# M7050E.net
KiCad netlist of a schematic drawn in EAGLE
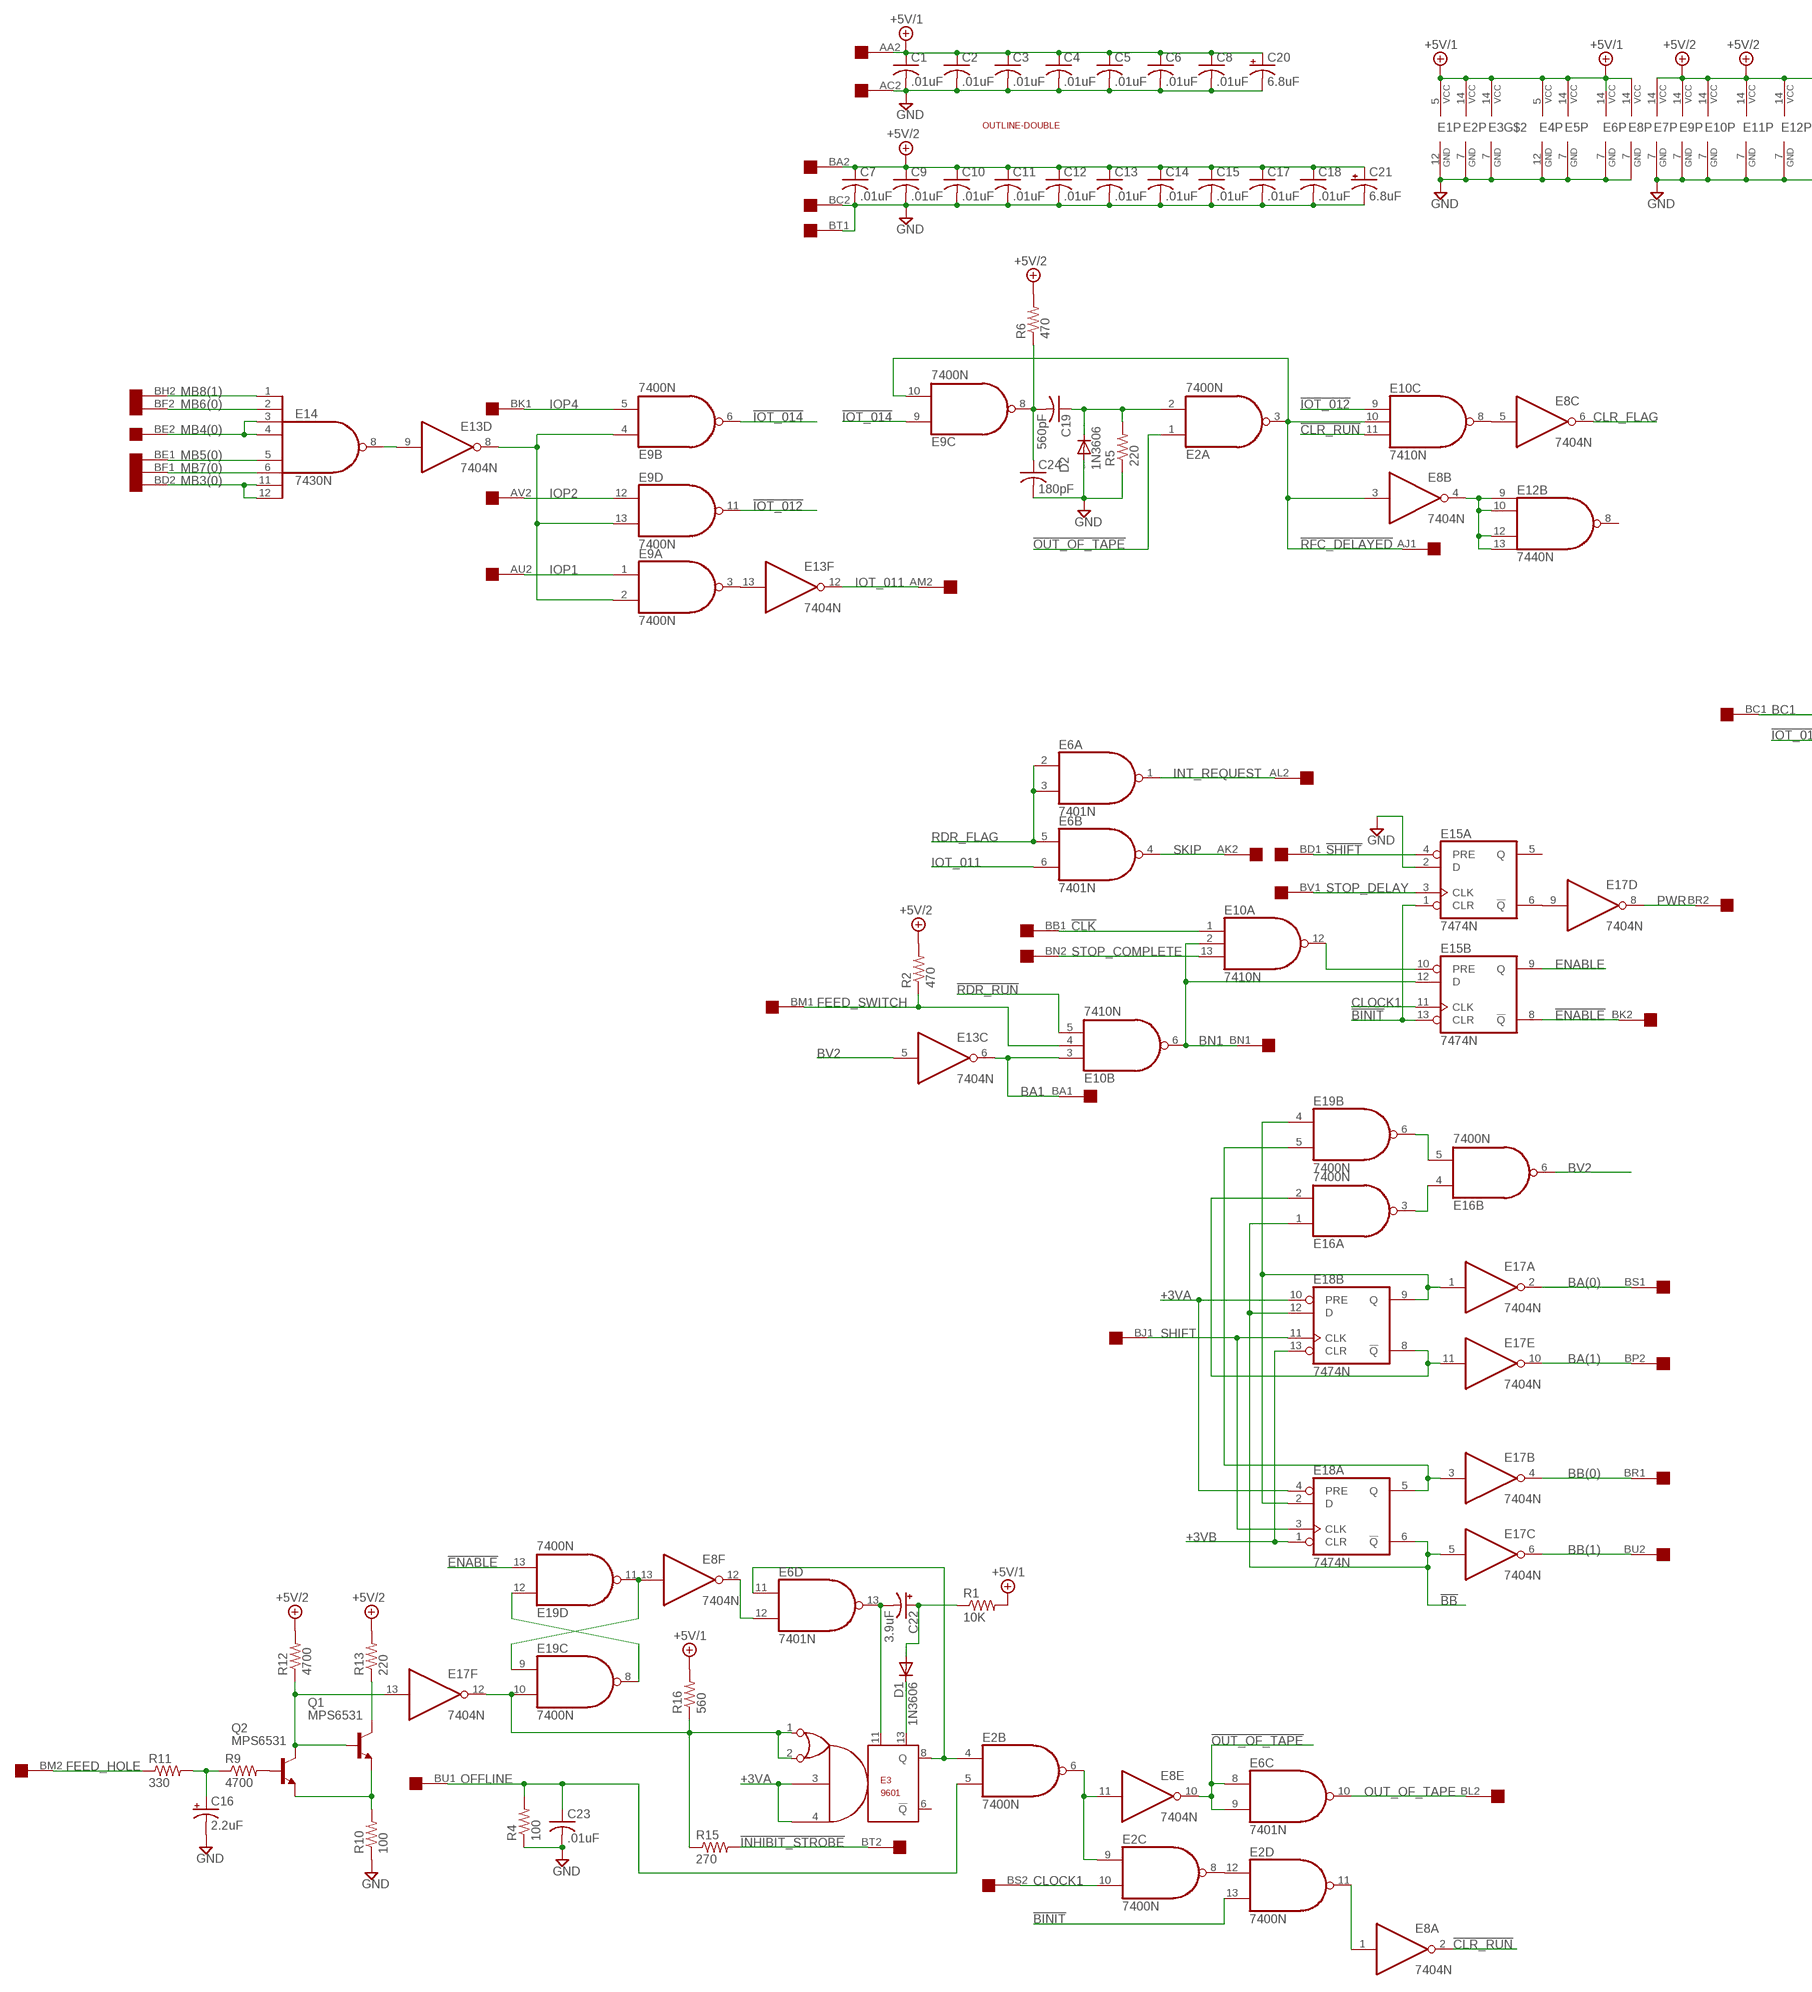
[diagram p0: schematic, sheet 1, part 1 of 2]
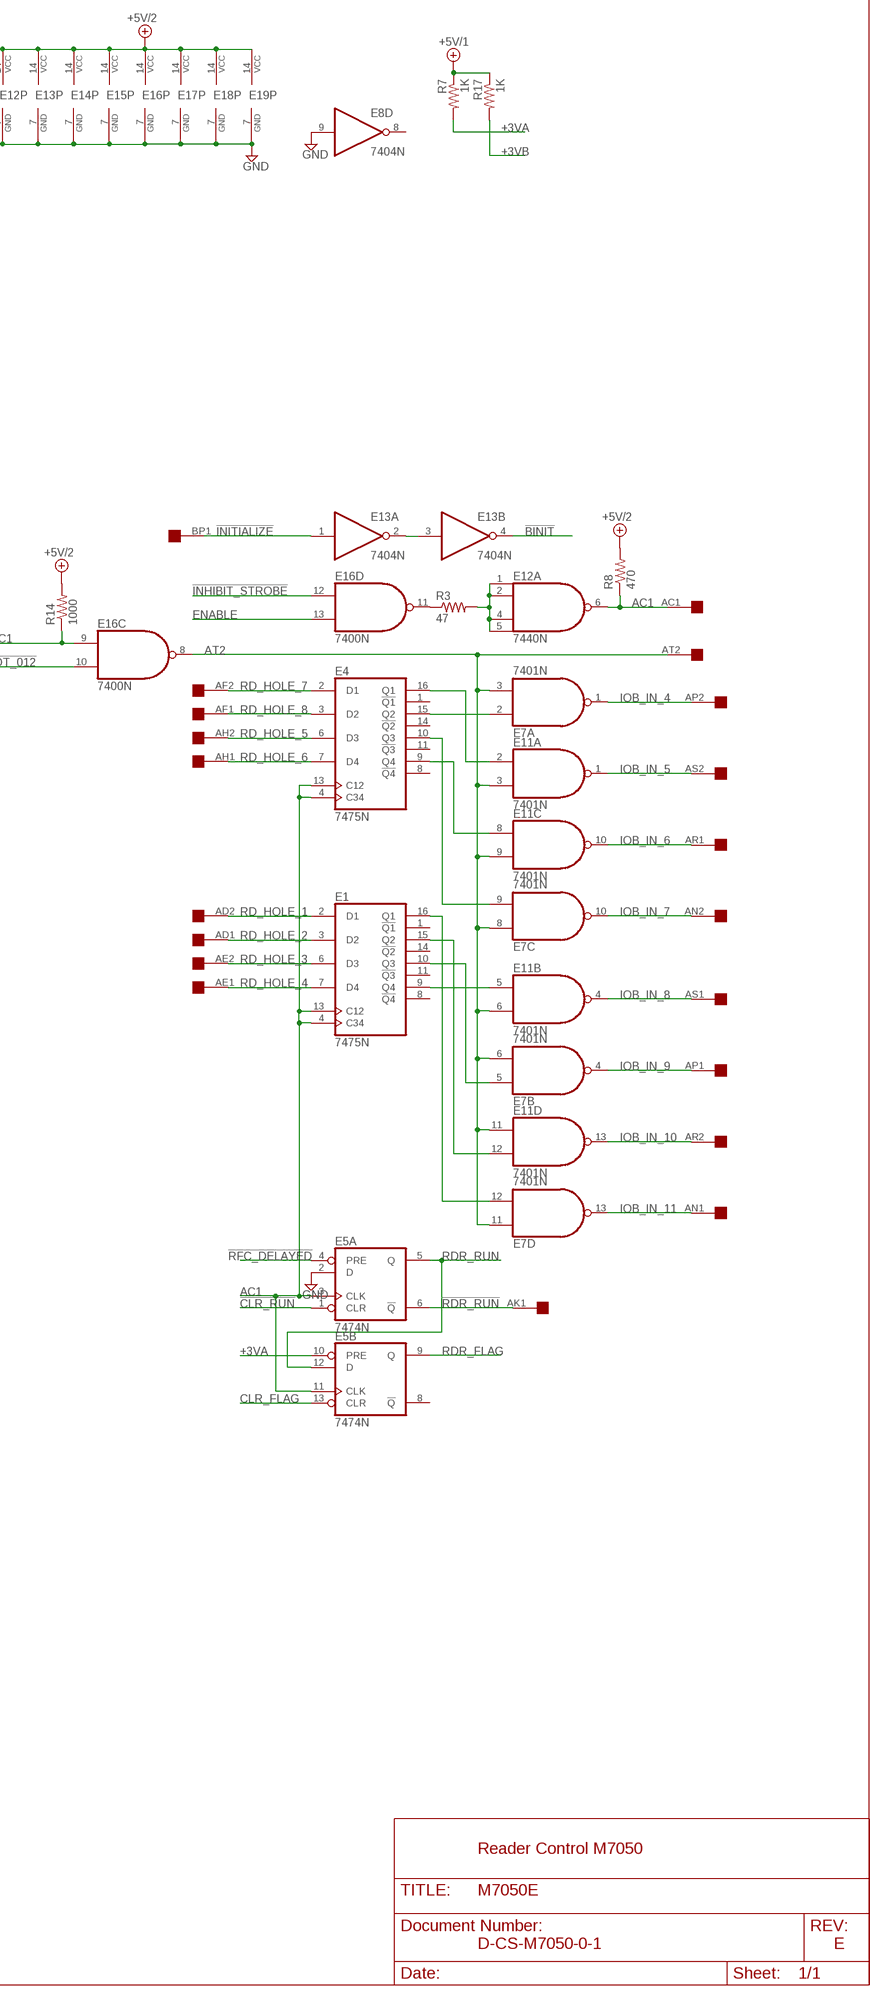
[diagram p1: schematic, sheet 1, part 2 of 2]

(export (version "E")
  (design (tool "Eeschema 10.0.6"))
  (components
    (comp (ref "C1")
      (value ".01uF")
      (footprint "eagle-import:C075-032X103")
      (libsource (lib "eagle-import") (part "C-US075-032X103"))
    )
    (comp (ref "C2")
      (value ".01uF")
      (footprint "eagle-import:C075-032X103")
      (libsource (lib "eagle-import") (part "C-US075-032X103"))
    )
    (comp (ref "C3")
      (value ".01uF")
      (footprint "eagle-import:C075-032X103")
      (libsource (lib "eagle-import") (part "C-US075-032X103"))
    )
    (comp (ref "C4")
      (value ".01uF")
      (footprint "eagle-import:C075-032X103")
      (libsource (lib "eagle-import") (part "C-US075-032X103"))
    )
    (comp (ref "C5")
      (value ".01uF")
      (footprint "eagle-import:C050-025X075")
      (libsource (lib "eagle-import") (part "C-US050-025X075"))
    )
    (comp (ref "C6")
      (value ".01uF")
      (footprint "eagle-import:C075-032X103")
      (libsource (lib "eagle-import") (part "C-US075-032X103"))
    )
    (comp (ref "C7")
      (value ".01uF")
      (footprint "eagle-import:C050-025X075")
      (libsource (lib "eagle-import") (part "C-US050-025X075"))
    )
    (comp (ref "C8")
      (value ".01uF")
      (footprint "eagle-import:C075-032X103")
      (libsource (lib "eagle-import") (part "C-US075-032X103"))
    )
    (comp (ref "C9")
      (value ".01uF")
      (footprint "eagle-import:C075-032X103")
      (libsource (lib "eagle-import") (part "C-US075-032X103"))
    )
    (comp (ref "C10")
      (value ".01uF")
      (footprint "eagle-import:C050-025X075")
      (libsource (lib "eagle-import") (part "C-US050-025X075"))
    )
    (comp (ref "C11")
      (value ".01uF")
      (footprint "eagle-import:C075-032X103")
      (libsource (lib "eagle-import") (part "C-US075-032X103"))
    )
    (comp (ref "C12")
      (value ".01uF")
      (footprint "eagle-import:C075-032X103")
      (libsource (lib "eagle-import") (part "C-US075-032X103"))
    )
    (comp (ref "C13")
      (value ".01uF")
      (footprint "eagle-import:C050-025X075")
      (libsource (lib "eagle-import") (part "C-US050-025X075"))
    )
    (comp (ref "C14")
      (value ".01uF")
      (footprint "eagle-import:C075-032X103")
      (libsource (lib "eagle-import") (part "C-US075-032X103"))
    )
    (comp (ref "C15")
      (value ".01uF")
      (footprint "eagle-import:C075-032X103")
      (libsource (lib "eagle-import") (part "C-US075-032X103"))
    )
    (comp (ref "C16")
      (value "2.2uF")
      (footprint "eagle-import:E12-8")
      (libsource (lib "eagle-import") (part "CPOL-USE20-8AXIAL"))
    )
    (comp (ref "C17")
      (value ".01uF")
      (footprint "eagle-import:C075-032X103")
      (libsource (lib "eagle-import") (part "C-US075-032X103"))
    )
    (comp (ref "C18")
      (value ".01uF")
      (footprint "eagle-import:C075-032X103")
      (libsource (lib "eagle-import") (part "C-US075-032X103"))
    )
    (comp (ref "C19")
      (value "560pF")
      (footprint "eagle-import:C050-025X075")
      (libsource (lib "eagle-import") (part "C-US050-025X075"))
    )
    (comp (ref "C20")
      (value "6.8uF")
      (footprint "eagle-import:E12-8")
      (libsource (lib "eagle-import") (part "CPOL-USE20-8AXIAL"))
    )
    (comp (ref "C21")
      (value "6.8uF")
      (footprint "eagle-import:E12-8")
      (libsource (lib "eagle-import") (part "CPOL-USE20-8AXIAL"))
    )
    (comp (ref "C22")
      (value "3.9uF")
      (footprint "eagle-import:E15-5")
      (libsource (lib "eagle-import") (part "CPOL-USE15-5AXIAL"))
    )
    (comp (ref "C23")
      (value ".01uF")
      (footprint "eagle-import:C075-032X103")
      (libsource (lib "eagle-import") (part "C-US075-032X103"))
    )
    (comp (ref "C24")
      (value "180pF")
      (footprint "eagle-import:C075-032X103")
      (libsource (lib "eagle-import") (part "C-US075-032X103"))
    )
    (comp (ref "D1")
      (value "1N3606")
      (footprint "eagle-import:DO35-10")
      (libsource (lib "eagle-import") (part "1N4148DO35-10"))
    )
    (comp (ref "D2")
      (value "1N3606")
      (footprint "eagle-import:DO35-10")
      (libsource (lib "eagle-import") (part "1N4148DO35-10"))
    )
    (comp (ref "E1")
      (value "7475N")
      (footprint "eagle-import:DIL16")
      (libsource (lib "eagle-import") (part "7475N"))
    )
    (comp (ref "E2")
      (value "7400N")
      (footprint "eagle-import:DIL14")
      (libsource (lib "eagle-import") (part "7400N"))
    )
    (comp (ref "E3")
      (value "9601")
      (footprint "eagle-import:DIL14")
      (libsource (lib "eagle-import") (part "9601"))
    )
    (comp (ref "E4")
      (value "7475N")
      (footprint "eagle-import:DIL16")
      (libsource (lib "eagle-import") (part "7475N"))
    )
    (comp (ref "E5")
      (value "7474N")
      (footprint "eagle-import:DIL14")
      (libsource (lib "eagle-import") (part "7474NS"))
    )
    (comp (ref "E6")
      (value "7401N")
      (footprint "eagle-import:DIL14")
      (libsource (lib "eagle-import") (part "7401NLS"))
    )
    (comp (ref "E7")
      (value "7401N")
      (footprint "eagle-import:DIL14")
      (libsource (lib "eagle-import") (part "7401NLS"))
    )
    (comp (ref "E8")
      (value "7404N")
      (footprint "eagle-import:DIL14")
      (libsource (lib "eagle-import") (part "7404N"))
    )
    (comp (ref "E9")
      (value "7400N")
      (footprint "eagle-import:DIL14")
      (libsource (lib "eagle-import") (part "7400N"))
    )
    (comp (ref "E10")
      (value "7410N")
      (footprint "eagle-import:DIL14")
      (libsource (lib "eagle-import") (part "7410N"))
    )
    (comp (ref "E11")
      (value "7401N")
      (footprint "eagle-import:DIL14")
      (libsource (lib "eagle-import") (part "7401NLS"))
    )
    (comp (ref "E12")
      (value "7440N")
      (footprint "eagle-import:DIL14")
      (libsource (lib "eagle-import") (part "7420NS"))
    )
    (comp (ref "E13")
      (value "7404N")
      (footprint "eagle-import:DIL14")
      (libsource (lib "eagle-import") (part "7404N"))
    )
    (comp (ref "E14")
      (value "7430N")
      (footprint "eagle-import:DIL14")
      (libsource (lib "eagle-import") (part "7430N"))
    )
    (comp (ref "E15")
      (value "7474N")
      (footprint "eagle-import:DIL14")
      (libsource (lib "eagle-import") (part "7474NS"))
    )
    (comp (ref "E16")
      (value "7400N")
      (footprint "eagle-import:DIL14")
      (libsource (lib "eagle-import") (part "7400N"))
    )
    (comp (ref "E17")
      (value "7404N")
      (footprint "eagle-import:DIL14")
      (libsource (lib "eagle-import") (part "7404N"))
    )
    (comp (ref "E18")
      (value "7474N")
      (footprint "eagle-import:DIL14")
      (libsource (lib "eagle-import") (part "7474NS"))
    )
    (comp (ref "E19")
      (value "7400N")
      (footprint "eagle-import:DIL14")
      (libsource (lib "eagle-import") (part "7400N"))
    )
    (comp (ref "Q1")
      (value "MPS6531")
      (footprint "eagle-import:TO5")
      (libsource (lib "eagle-import") (part "2N2102"))
    )
    (comp (ref "Q2")
      (value "MPS6531")
      (footprint "eagle-import:TO5")
      (libsource (lib "eagle-import") (part "2N2102"))
    )
    (comp (ref "R1")
      (value "10K")
      (footprint "eagle-import:0207_10")
      (libsource (lib "eagle-import") (part "R-US_0207/10"))
    )
    (comp (ref "R2")
      (value "470")
      (footprint "eagle-import:0207_10")
      (libsource (lib "eagle-import") (part "R-US_0207/10"))
    )
    (comp (ref "R3")
      (value "47")
      (footprint "eagle-import:0207_10")
      (libsource (lib "eagle-import") (part "R-US_0207/10"))
    )
    (comp (ref "R4")
      (value "100")
      (footprint "eagle-import:0207_10")
      (libsource (lib "eagle-import") (part "R-US_0207/10"))
    )
    (comp (ref "R5")
      (value "220")
      (footprint "eagle-import:0207_10")
      (libsource (lib "eagle-import") (part "R-US_0207/10"))
    )
    (comp (ref "R6")
      (value "470")
      (footprint "eagle-import:0207_10")
      (libsource (lib "eagle-import") (part "R-US_0207/10"))
    )
    (comp (ref "R7")
      (value "1K")
      (footprint "eagle-import:0207_10")
      (libsource (lib "eagle-import") (part "R-US_0207/10"))
    )
    (comp (ref "R8")
      (value "470")
      (footprint "eagle-import:0207_10")
      (libsource (lib "eagle-import") (part "R-US_0207/10"))
    )
    (comp (ref "R9")
      (value "4700")
      (footprint "eagle-import:0207_10")
      (libsource (lib "eagle-import") (part "R-US_0207/10"))
    )
    (comp (ref "R10")
      (value "100")
      (footprint "eagle-import:0207_10")
      (libsource (lib "eagle-import") (part "R-US_0207/10"))
    )
    (comp (ref "R11")
      (value "330")
      (footprint "eagle-import:0207_10")
      (libsource (lib "eagle-import") (part "R-US_0207/10"))
    )
    (comp (ref "R12")
      (value "4700")
      (footprint "eagle-import:0207_10")
      (libsource (lib "eagle-import") (part "R-US_0207/10"))
    )
    (comp (ref "R13")
      (value "220")
      (footprint "eagle-import:0207_10")
      (libsource (lib "eagle-import") (part "R-US_0207/10"))
    )
    (comp (ref "R14")
      (value "1000")
      (footprint "eagle-import:0207_10")
      (libsource (lib "eagle-import") (part "R-US_0207/10"))
    )
    (comp (ref "R15")
      (value "270")
      (footprint "eagle-import:0207_10")
      (libsource (lib "eagle-import") (part "R-US_0207/10"))
    )
    (comp (ref "R16")
      (value "560")
      (footprint "eagle-import:0207_10")
      (libsource (lib "eagle-import") (part "R-US_0207/10"))
    )
    (comp (ref "R17")
      (value "1K")
      (footprint "eagle-import:0207_10")
      (libsource (lib "eagle-import") (part "R-US_0207/10"))
    )
    (comp (ref "U$5")
      (value "DOUBLE")
      (footprint "eagle-import:EDGE-CON4")
      (libsource (lib "eagle-import") (part "DOUBLE"))
    )
    (comp (ref "U$6")
      (value "OUTLINE-DOUBLE")
      (footprint "eagle-import:DOUBLE")
      (libsource (lib "eagle-import") (part "OUTLINE-DOUBLE"))
    )
  )
  (nets
    (net (code "1") (name "+5V{slash}1") (class "Default")
      (node (ref "C1") (pin "1") (pinfunction "1_1") (pintype "passive"))
      (node (ref "C2") (pin "1") (pinfunction "1_1") (pintype "passive"))
      (node (ref "C20") (pin "+") (pinfunction "+_+") (pintype "passive"))
      (node (ref "C3") (pin "1") (pinfunction "1_1") (pintype "passive"))
      (node (ref "C4") (pin "1") (pinfunction "1_1") (pintype "passive"))
      (node (ref "C5") (pin "1") (pinfunction "1_1") (pintype "passive"))
      (node (ref "C6") (pin "1") (pinfunction "1_1") (pintype "passive"))
      (node (ref "C8") (pin "1") (pinfunction "1_1") (pintype "passive"))
      (node (ref "E1") (pin "5") (pinfunction "VCC_5") (pintype "power_in"))
      (node (ref "E2") (pin "14") (pinfunction "VCC_14") (pintype "power_in"))
      (node (ref "E3") (pin "14") (pinfunction "VCC_14") (pintype "power_in"))
      (node (ref "E4") (pin "5") (pinfunction "VCC_5") (pintype "power_in"))
      (node (ref "E5") (pin "14") (pinfunction "VCC_14") (pintype "power_in"))
      (node (ref "E6") (pin "14") (pinfunction "VCC_14") (pintype "power_in"))
      (node (ref "E8") (pin "14") (pinfunction "VCC_14") (pintype "power_in"))
      (node (ref "R1") (pin "2") (pinfunction "2_2") (pintype "passive"))
      (node (ref "R16") (pin "2") (pinfunction "2_2") (pintype "passive"))
      (node (ref "R17") (pin "1") (pinfunction "1_1") (pintype "passive"))
      (node (ref "R7") (pin "1") (pinfunction "1_1") (pintype "passive"))
      (node (ref "U$5") (pin "AA2") (pinfunction "1_AA2") (pintype "bidirectional"))
    )
    (net (code "2") (name "+5V{slash}2") (class "Default")
      (node (ref "C10") (pin "1") (pinfunction "1_1") (pintype "passive"))
      (node (ref "C11") (pin "1") (pinfunction "1_1") (pintype "passive"))
      (node (ref "C12") (pin "1") (pinfunction "1_1") (pintype "passive"))
      (node (ref "C13") (pin "1") (pinfunction "1_1") (pintype "passive"))
      (node (ref "C14") (pin "1") (pinfunction "1_1") (pintype "passive"))
      (node (ref "C15") (pin "1") (pinfunction "1_1") (pintype "passive"))
      (node (ref "C17") (pin "1") (pinfunction "1_1") (pintype "passive"))
      (node (ref "C18") (pin "1") (pinfunction "1_1") (pintype "passive"))
      (node (ref "C21") (pin "+") (pinfunction "+_+") (pintype "passive"))
      (node (ref "C7") (pin "1") (pinfunction "1_1") (pintype "passive"))
      (node (ref "C9") (pin "1") (pinfunction "1_1") (pintype "passive"))
      (node (ref "E10") (pin "14") (pinfunction "VCC_14") (pintype "power_in"))
      (node (ref "E11") (pin "14") (pinfunction "VCC_14") (pintype "power_in"))
      (node (ref "E12") (pin "14") (pinfunction "VCC_14") (pintype "power_in"))
      (node (ref "E13") (pin "14") (pinfunction "VCC_14") (pintype "power_in"))
      (node (ref "E14") (pin "14") (pinfunction "VCC_14") (pintype "power_in"))
      (node (ref "E15") (pin "14") (pinfunction "VCC_14") (pintype "power_in"))
      (node (ref "E16") (pin "14") (pinfunction "VCC_14") (pintype "power_in"))
      (node (ref "E17") (pin "14") (pinfunction "VCC_14") (pintype "power_in"))
      (node (ref "E18") (pin "14") (pinfunction "VCC_14") (pintype "power_in"))
      (node (ref "E19") (pin "14") (pinfunction "VCC_14") (pintype "power_in"))
      (node (ref "E7") (pin "14") (pinfunction "VCC_14") (pintype "power_in"))
      (node (ref "E9") (pin "14") (pinfunction "VCC_14") (pintype "power_in"))
      (node (ref "R12") (pin "2") (pinfunction "2_2") (pintype "passive"))
      (node (ref "R13") (pin "2") (pinfunction "2_2") (pintype "passive"))
      (node (ref "R14") (pin "2") (pinfunction "2_2") (pintype "passive"))
      (node (ref "R2") (pin "2") (pinfunction "2_2") (pintype "passive"))
      (node (ref "R6") (pin "2") (pinfunction "2_2") (pintype "passive"))
      (node (ref "R8") (pin "2") (pinfunction "2_2") (pintype "passive"))
      (node (ref "U$5") (pin "BA2") (pinfunction "1_BA2") (pintype "bidirectional"))
    )
    (net (code "3") (name "/+3VA") (class "Default")
      (node (ref "E18") (pin "10") (pinfunction "PRE_10") (pintype "input"))
      (node (ref "E18") (pin "4") (pinfunction "PRE_4") (pintype "input"))
      (node (ref "E3") (pin "3") (pinfunction "P$3_3") (pintype "input"))
      (node (ref "E3") (pin "4") (pinfunction "P$4_4") (pintype "input"))
      (node (ref "E5") (pin "10") (pinfunction "PRE_10") (pintype "input"))
      (node (ref "R7") (pin "2") (pinfunction "2_2") (pintype "passive"))
    )
    (net (code "4") (name "/+3VB") (class "Default")
      (node (ref "E18") (pin "1") (pinfunction "CLR_1") (pintype "input"))
      (node (ref "E18") (pin "13") (pinfunction "CLR_13") (pintype "input"))
      (node (ref "R17") (pin "2") (pinfunction "2_2") (pintype "passive"))
    )
    (net (code "5") (name "/AC1") (class "Default")
      (node (ref "E1") (pin "13") (pinfunction "C12_13") (pintype "input"))
      (node (ref "E1") (pin "4") (pinfunction "C34_4") (pintype "input"))
      (node (ref "E12") (pin "6") (pinfunction "O_6") (pintype "output"))
      (node (ref "E4") (pin "13") (pinfunction "C12_13") (pintype "input"))
      (node (ref "E4") (pin "4") (pinfunction "C34_4") (pintype "input"))
      (node (ref "E5") (pin "11") (pinfunction "CLK_11") (pintype "input"))
      (node (ref "E5") (pin "3") (pinfunction "CLK_3") (pintype "input"))
      (node (ref "R8") (pin "1") (pinfunction "1_1") (pintype "passive"))
      (node (ref "U$5") (pin "AC1") (pinfunction "1_AC1") (pintype "bidirectional"))
    )
    (net (code "6") (name "/AT2") (class "Default")
      (node (ref "E11") (pin "11") (pinfunction "I0_11") (pintype "input"))
      (node (ref "E11") (pin "3") (pinfunction "I1_3") (pintype "input"))
      (node (ref "E11") (pin "6") (pinfunction "I1_6") (pintype "input"))
      (node (ref "E11") (pin "9") (pinfunction "I1_9") (pintype "input"))
      (node (ref "E16") (pin "8") (pinfunction "O_8") (pintype "output"))
      (node (ref "E7") (pin "11") (pinfunction "I0_11") (pintype "input"))
      (node (ref "E7") (pin "3") (pinfunction "I1_3") (pintype "input"))
      (node (ref "E7") (pin "6") (pinfunction "I1_6") (pintype "input"))
      (node (ref "E7") (pin "8") (pinfunction "I0_8") (pintype "input"))
      (node (ref "U$5") (pin "AT2") (pinfunction "1_AT2") (pintype "bidirectional"))
    )
    (net (code "7") (name "/BA(0)") (class "Default")
      (node (ref "E17") (pin "2") (pinfunction "O_2") (pintype "output"))
      (node (ref "U$5") (pin "BS1") (pinfunction "1_BS1") (pintype "bidirectional"))
    )
    (net (code "8") (name "/BA(1)") (class "Default")
      (node (ref "E17") (pin "10") (pinfunction "O_10") (pintype "output"))
      (node (ref "U$5") (pin "BP2") (pinfunction "1_BP2") (pintype "bidirectional"))
    )
    (net (code "9") (name "/BA1") (class "Default")
      (node (ref "E10") (pin "3") (pinfunction "I0_3") (pintype "input"))
      (node (ref "E13") (pin "6") (pinfunction "O_6") (pintype "output"))
      (node (ref "U$5") (pin "BA1") (pinfunction "1_BA1") (pintype "bidirectional"))
    )
    (net (code "10") (name "/BB(0)") (class "Default")
      (node (ref "E17") (pin "4") (pinfunction "O_4") (pintype "output"))
      (node (ref "U$5") (pin "BR1") (pinfunction "1_BR1") (pintype "bidirectional"))
    )
    (net (code "11") (name "/BB(1)") (class "Default")
      (node (ref "E17") (pin "6") (pinfunction "O_6") (pintype "output"))
      (node (ref "U$5") (pin "BU2") (pinfunction "1_BU2") (pintype "bidirectional"))
    )
    (net (code "12") (name "/BC1") (class "Default")
      (node (ref "E16") (pin "9") (pinfunction "I0_9") (pintype "input"))
      (node (ref "R14") (pin "1") (pinfunction "1_1") (pintype "passive"))
      (node (ref "U$5") (pin "BC1") (pinfunction "1_BC1") (pintype "bidirectional"))
    )
    (net (code "13") (name "/BN1") (class "Default")
      (node (ref "E10") (pin "2") (pinfunction "I1_2") (pintype "input"))
      (node (ref "E10") (pin "6") (pinfunction "O_6") (pintype "output"))
      (node (ref "E15") (pin "12") (pinfunction "D_12") (pintype "input"))
      (node (ref "U$5") (pin "BN1") (pinfunction "1_BN1") (pintype "bidirectional"))
    )
    (net (code "14") (name "/BV2") (class "Default")
      (node (ref "E13") (pin "5") (pinfunction "I_5") (pintype "input"))
      (node (ref "E16") (pin "6") (pinfunction "O_6") (pintype "output"))
    )
    (net (code "15") (name "/CLOCK1") (class "Default")
      (node (ref "E15") (pin "11") (pinfunction "CLK_11") (pintype "input"))
      (node (ref "E2") (pin "10") (pinfunction "I1_10") (pintype "input"))
      (node (ref "U$5") (pin "BS2") (pinfunction "1_BS2") (pintype "bidirectional"))
    )
    (net (code "16") (name "/CLR_FLAG") (class "Default")
      (node (ref "E5") (pin "13") (pinfunction "CLR_13") (pintype "input"))
      (node (ref "E8") (pin "6") (pinfunction "O_6") (pintype "output"))
    )
    (net (code "17") (name "/ENABLE") (class "Default")
      (node (ref "E15") (pin "9") (pinfunction "Q_9") (pintype "output"))
      (node (ref "E16") (pin "13") (pinfunction "I1_13") (pintype "input"))
    )
    (net (code "18") (name "/FEED_HOLE") (class "Default")
      (node (ref "R11") (pin "1") (pinfunction "1_1") (pintype "passive"))
      (node (ref "U$5") (pin "BM2") (pinfunction "1_BM2") (pintype "bidirectional"))
    )
    (net (code "19") (name "/FEED_SWITCH") (class "Default")
      (node (ref "E10") (pin "4") (pinfunction "I1_4") (pintype "input"))
      (node (ref "R2") (pin "1") (pinfunction "1_1") (pintype "passive"))
      (node (ref "U$5") (pin "BM1") (pinfunction "1_BM1") (pintype "bidirectional"))
    )
    (net (code "20") (name "/INT_REQUEST") (class "Default")
      (node (ref "E6") (pin "1") (pinfunction "O_1") (pintype "open_collector"))
      (node (ref "U$5") (pin "AL2") (pinfunction "1_AL2") (pintype "bidirectional"))
    )
    (net (code "21") (name "/IOB_IN_4") (class "Default")
      (node (ref "E7") (pin "1") (pinfunction "O_1") (pintype "open_collector"))
      (node (ref "U$5") (pin "AP2") (pinfunction "1_AP2") (pintype "bidirectional"))
    )
    (net (code "22") (name "/IOB_IN_5") (class "Default")
      (node (ref "E11") (pin "1") (pinfunction "O_1") (pintype "open_collector"))
      (node (ref "U$5") (pin "AS2") (pinfunction "1_AS2") (pintype "bidirectional"))
    )
    (net (code "23") (name "/IOB_IN_6") (class "Default")
      (node (ref "E11") (pin "10") (pinfunction "O_10") (pintype "open_collector"))
      (node (ref "U$5") (pin "AR1") (pinfunction "1_AR1") (pintype "bidirectional"))
    )
    (net (code "24") (name "/IOB_IN_7") (class "Default")
      (node (ref "E7") (pin "10") (pinfunction "O_10") (pintype "open_collector"))
      (node (ref "U$5") (pin "AN2") (pinfunction "1_AN2") (pintype "bidirectional"))
    )
    (net (code "25") (name "/IOB_IN_8") (class "Default")
      (node (ref "E11") (pin "4") (pinfunction "O_4") (pintype "open_collector"))
      (node (ref "U$5") (pin "AS1") (pinfunction "1_AS1") (pintype "bidirectional"))
    )
    (net (code "26") (name "/IOB_IN_9") (class "Default")
      (node (ref "E7") (pin "4") (pinfunction "O_4") (pintype "open_collector"))
      (node (ref "U$5") (pin "AP1") (pinfunction "1_AP1") (pintype "bidirectional"))
    )
    (net (code "27") (name "/IOB_IN_10") (class "Default")
      (node (ref "E11") (pin "13") (pinfunction "O_13") (pintype "open_collector"))
      (node (ref "U$5") (pin "AR2") (pinfunction "1_AR2") (pintype "bidirectional"))
    )
    (net (code "28") (name "/IOB_IN_11") (class "Default")
      (node (ref "E7") (pin "13") (pinfunction "O_13") (pintype "open_collector"))
      (node (ref "U$5") (pin "AN1") (pinfunction "1_AN1") (pintype "bidirectional"))
    )
    (net (code "29") (name "/IOP1") (class "Default")
      (node (ref "E9") (pin "1") (pinfunction "I0_1") (pintype "input"))
      (node (ref "U$5") (pin "AU2") (pinfunction "1_AU2") (pintype "bidirectional"))
    )
    (net (code "30") (name "/IOP2") (class "Default")
      (node (ref "E9") (pin "12") (pinfunction "I0_12") (pintype "input"))
      (node (ref "U$5") (pin "AV2") (pinfunction "1_AV2") (pintype "bidirectional"))
    )
    (net (code "31") (name "/IOP4") (class "Default")
      (node (ref "E9") (pin "5") (pinfunction "I1_5") (pintype "input"))
      (node (ref "U$5") (pin "BK1") (pinfunction "1_BK1") (pintype "bidirectional"))
    )
    (net (code "32") (name "/IOT_011") (class "Default")
      (node (ref "E13") (pin "12") (pinfunction "O_12") (pintype "output"))
      (node (ref "E6") (pin "6") (pinfunction "I1_6") (pintype "input"))
      (node (ref "U$5") (pin "AM2") (pinfunction "1_AM2") (pintype "bidirectional"))
    )
    (net (code "33") (name "/MB3(0)") (class "Default")
      (node (ref "E14") (pin "11") (pinfunction "I6_11") (pintype "input"))
      (node (ref "E14") (pin "12") (pinfunction "I7_12") (pintype "input"))
      (node (ref "U$5") (pin "BD2") (pinfunction "1_BD2") (pintype "bidirectional"))
    )
    (net (code "34") (name "/MB4(0)") (class "Default")
      (node (ref "E14") (pin "3") (pinfunction "I2_3") (pintype "input"))
      (node (ref "E14") (pin "4") (pinfunction "I3_4") (pintype "input"))
      (node (ref "U$5") (pin "BE2") (pinfunction "1_BE2") (pintype "bidirectional"))
    )
    (net (code "35") (name "/MB5(0)") (class "Default")
      (node (ref "E14") (pin "5") (pinfunction "I4_5") (pintype "input"))
      (node (ref "U$5") (pin "BE1") (pinfunction "1_BE1") (pintype "bidirectional"))
    )
    (net (code "36") (name "/MB6(0)") (class "Default")
      (node (ref "E14") (pin "2") (pinfunction "I1_2") (pintype "input"))
      (node (ref "U$5") (pin "BF2") (pinfunction "1_BF2") (pintype "bidirectional"))
    )
    (net (code "37") (name "/MB7(0)") (class "Default")
      (node (ref "E14") (pin "6") (pinfunction "I5_6") (pintype "input"))
      (node (ref "U$5") (pin "BF1") (pinfunction "1_BF1") (pintype "bidirectional"))
    )
    (net (code "38") (name "/MB8(1)") (class "Default")
      (node (ref "E14") (pin "1") (pinfunction "I0_1") (pintype "input"))
      (node (ref "U$5") (pin "BH2") (pinfunction "1_BH2") (pintype "bidirectional"))
    )
    (net (code "39") (name "/OFFLINE") (class "Default")
      (node (ref "C23") (pin "1") (pinfunction "1_1") (pintype "passive"))
      (node (ref "E2") (pin "5") (pinfunction "I1_5") (pintype "input"))
      (node (ref "R4") (pin "2") (pinfunction "2_2") (pintype "passive"))
      (node (ref "U$5") (pin "BU1") (pinfunction "1_BU1") (pintype "bidirectional"))
    )
    (net (code "40") (name "/OUT_OF_TAPE") (class "Default")
      (node (ref "E6") (pin "10") (pinfunction "O_10") (pintype "open_collector"))
      (node (ref "U$5") (pin "BL2") (pinfunction "1_BL2") (pintype "bidirectional"))
    )
    (net (code "41") (name "/PWR") (class "Default")
      (node (ref "E17") (pin "8") (pinfunction "O_8") (pintype "output"))
      (node (ref "U$5") (pin "BR2") (pinfunction "1_BR2") (pintype "bidirectional"))
    )
    (net (code "42") (name "/RDR_FLAG") (class "Default")
      (node (ref "E5") (pin "9") (pinfunction "Q_9") (pintype "output"))
      (node (ref "E6") (pin "2") (pinfunction "I0_2") (pintype "input"))
      (node (ref "E6") (pin "3") (pinfunction "I1_3") (pintype "input"))
      (node (ref "E6") (pin "5") (pinfunction "I0_5") (pintype "input"))
    )
    (net (code "43") (name "/RDR_RUN") (class "Default")
      (node (ref "E5") (pin "12") (pinfunction "D_12") (pintype "input"))
      (node (ref "E5") (pin "5") (pinfunction "Q_5") (pintype "output"))
    )
    (net (code "44") (name "/RD_HOLE_1") (class "Default")
      (node (ref "E1") (pin "2") (pinfunction "D1_2") (pintype "input"))
      (node (ref "U$5") (pin "AD2") (pinfunction "1_AD2") (pintype "bidirectional"))
    )
    (net (code "45") (name "/RD_HOLE_2") (class "Default")
      (node (ref "E1") (pin "3") (pinfunction "D2_3") (pintype "input"))
      (node (ref "U$5") (pin "AD1") (pinfunction "1_AD1") (pintype "bidirectional"))
    )
    (net (code "46") (name "/RD_HOLE_3") (class "Default")
      (node (ref "E1") (pin "6") (pinfunction "D3_6") (pintype "input"))
      (node (ref "U$5") (pin "AE2") (pinfunction "1_AE2") (pintype "bidirectional"))
    )
    (net (code "47") (name "/RD_HOLE_4") (class "Default")
      (node (ref "E1") (pin "7") (pinfunction "D4_7") (pintype "input"))
      (node (ref "U$5") (pin "AE1") (pinfunction "1_AE1") (pintype "bidirectional"))
    )
    (net (code "48") (name "/RD_HOLE_5") (class "Default")
      (node (ref "E4") (pin "6") (pinfunction "D3_6") (pintype "input"))
      (node (ref "U$5") (pin "AH2") (pinfunction "1_AH2") (pintype "bidirectional"))
    )
    (net (code "49") (name "/RD_HOLE_6") (class "Default")
      (node (ref "E4") (pin "7") (pinfunction "D4_7") (pintype "input"))
      (node (ref "U$5") (pin "AH1") (pinfunction "1_AH1") (pintype "bidirectional"))
    )
    (net (code "50") (name "/RD_HOLE_7") (class "Default")
      (node (ref "E4") (pin "2") (pinfunction "D1_2") (pintype "input"))
      (node (ref "U$5") (pin "AF2") (pinfunction "1_AF2") (pintype "bidirectional"))
    )
    (net (code "51") (name "/RD_HOLE_8") (class "Default")
      (node (ref "E4") (pin "3") (pinfunction "D2_3") (pintype "input"))
      (node (ref "U$5") (pin "AF1") (pinfunction "1_AF1") (pintype "bidirectional"))
    )
    (net (code "52") (name "/SHIFT") (class "Default")
      (node (ref "E18") (pin "11") (pinfunction "CLK_11") (pintype "input"))
      (node (ref "E18") (pin "3") (pinfunction "CLK_3") (pintype "input"))
      (node (ref "U$5") (pin "BJ1") (pinfunction "1_BJ1") (pintype "bidirectional"))
    )
    (net (code "53") (name "/SKIP") (class "Default")
      (node (ref "E6") (pin "4") (pinfunction "O_4") (pintype "open_collector"))
      (node (ref "U$5") (pin "AK2") (pinfunction "1_AK2") (pintype "bidirectional"))
    )
    (net (code "54") (name "/STOP_COMPLETE") (class "Default")
      (node (ref "E10") (pin "13") (pinfunction "I2_13") (pintype "input"))
      (node (ref "U$5") (pin "BN2") (pinfunction "1_BN2") (pintype "bidirectional"))
    )
    (net (code "55") (name "/STOP_DELAY") (class "Default")
      (node (ref "E15") (pin "3") (pinfunction "CLK_3") (pintype "input"))
      (node (ref "U$5") (pin "BV1") (pinfunction "1_BV1") (pintype "bidirectional"))
    )
    (net (code "56") (name "/~{BB}") (class "Default")
      (node (ref "E16") (pin "1") (pinfunction "I0_1") (pintype "input"))
      (node (ref "E17") (pin "5") (pinfunction "I_5") (pintype "input"))
      (node (ref "E18") (pin "12") (pinfunction "D_12") (pintype "input"))
      (node (ref "E18") (pin "6") (pinfunction "~{Q}_6") (pintype "output"))
    )
    (net (code "57") (name "/~{BINIT}") (class "Default")
      (node (ref "E13") (pin "4") (pinfunction "O_4") (pintype "output"))
      (node (ref "E15") (pin "1") (pinfunction "CLR_1") (pintype "input"))
      (node (ref "E15") (pin "13") (pinfunction "CLR_13") (pintype "input"))
      (node (ref "E2") (pin "13") (pinfunction "I1_13") (pintype "input"))
    )
    (net (code "58") (name "/~{CLK}") (class "Default")
      (node (ref "E10") (pin "1") (pinfunction "I0_1") (pintype "input"))
      (node (ref "U$5") (pin "BB1") (pinfunction "1_BB1") (pintype "bidirectional"))
    )
    (net (code "59") (name "/~{CLR_RUN}") (class "Default")
      (node (ref "E10") (pin "11") (pinfunction "I2_11") (pintype "input"))
      (node (ref "E5") (pin "1") (pinfunction "CLR_1") (pintype "input"))
      (node (ref "E8") (pin "2") (pinfunction "O_2") (pintype "output"))
    )
    (net (code "60") (name "/~{ENABLE}") (class "Default")
      (node (ref "E15") (pin "8") (pinfunction "~{Q}_8") (pintype "output"))
      (node (ref "E19") (pin "13") (pinfunction "I1_13") (pintype "input"))
      (node (ref "U$5") (pin "BK2") (pinfunction "1_BK2") (pintype "bidirectional"))
    )
    (net (code "61") (name "/~{INHIBIT_STROBE}") (class "Default")
      (node (ref "E16") (pin "12") (pinfunction "I0_12") (pintype "input"))
      (node (ref "R15") (pin "2") (pinfunction "2_2") (pintype "passive"))
      (node (ref "U$5") (pin "BT2") (pinfunction "1_BT2") (pintype "bidirectional"))
    )
    (net (code "62") (name "/~{INITIALIZE}") (class "Default")
      (node (ref "E13") (pin "1") (pinfunction "I_1") (pintype "input"))
      (node (ref "U$5") (pin "BP1") (pinfunction "1_BP1") (pintype "bidirectional"))
    )
    (net (code "63") (name "/~{IOT_012}") (class "Default")
      (node (ref "E10") (pin "9") (pinfunction "I0_9") (pintype "input"))
      (node (ref "E16") (pin "10") (pinfunction "I1_10") (pintype "input"))
      (node (ref "E9") (pin "11") (pinfunction "O_11") (pintype "output"))
    )
    (net (code "64") (name "/~{IOT_014}") (class "Default")
      (node (ref "E9") (pin "6") (pinfunction "O_6") (pintype "output"))
      (node (ref "E9") (pin "9") (pinfunction "I0_9") (pintype "input"))
    )
    (net (code "65") (name "/~{OUT_OF_TAPE}") (class "Default")
      (node (ref "E2") (pin "1") (pinfunction "I0_1") (pintype "input"))
      (node (ref "E6") (pin "8") (pinfunction "I0_8") (pintype "input"))
      (node (ref "E6") (pin "9") (pinfunction "I1_9") (pintype "input"))
      (node (ref "E8") (pin "10") (pinfunction "O_10") (pintype "output"))
    )
    (net (code "66") (name "/~{RDR_RUN}") (class "Default")
      (node (ref "E10") (pin "5") (pinfunction "I2_5") (pintype "input"))
      (node (ref "E5") (pin "6") (pinfunction "~{Q}_6") (pintype "output"))
      (node (ref "U$5") (pin "AK1") (pinfunction "1_AK1") (pintype "bidirectional"))
    )
    (net (code "67") (name "/~{RFC_DELAYED}") (class "Default")
      (node (ref "E10") (pin "10") (pinfunction "I1_10") (pintype "input"))
      (node (ref "E2") (pin "3") (pinfunction "O_3") (pintype "output"))
      (node (ref "E5") (pin "4") (pinfunction "PRE_4") (pintype "input"))
      (node (ref "E8") (pin "3") (pinfunction "I_3") (pintype "input"))
      (node (ref "E9") (pin "10") (pinfunction "I1_10") (pintype "input"))
      (node (ref "U$5") (pin "AJ1") (pinfunction "1_AJ1") (pintype "bidirectional"))
    )
    (net (code "68") (name "/~{SHIFT}") (class "Default")
      (node (ref "E15") (pin "4") (pinfunction "PRE_4") (pintype "input"))
      (node (ref "U$5") (pin "BD1") (pinfunction "1_BD1") (pintype "bidirectional"))
    )
    (net (code "69") (name "GND") (class "Default")
      (node (ref "C1") (pin "2") (pinfunction "2_2") (pintype "passive"))
      (node (ref "C10") (pin "2") (pinfunction "2_2") (pintype "passive"))
      (node (ref "C11") (pin "2") (pinfunction "2_2") (pintype "passive"))
      (node (ref "C12") (pin "2") (pinfunction "2_2") (pintype "passive"))
      (node (ref "C13") (pin "2") (pinfunction "2_2") (pintype "passive"))
      (node (ref "C14") (pin "2") (pinfunction "2_2") (pintype "passive"))
      (node (ref "C15") (pin "2") (pinfunction "2_2") (pintype "passive"))
      (node (ref "C16") (pin "-") (pinfunction "-_-") (pintype "passive"))
      (node (ref "C17") (pin "2") (pinfunction "2_2") (pintype "passive"))
      (node (ref "C18") (pin "2") (pinfunction "2_2") (pintype "passive"))
      (node (ref "C2") (pin "2") (pinfunction "2_2") (pintype "passive"))
      (node (ref "C20") (pin "-") (pinfunction "-_-") (pintype "passive"))
      (node (ref "C21") (pin "-") (pinfunction "-_-") (pintype "passive"))
      (node (ref "C23") (pin "2") (pinfunction "2_2") (pintype "passive"))
      (node (ref "C24") (pin "2") (pinfunction "2_2") (pintype "passive"))
      (node (ref "C3") (pin "2") (pinfunction "2_2") (pintype "passive"))
      (node (ref "C4") (pin "2") (pinfunction "2_2") (pintype "passive"))
      (node (ref "C5") (pin "2") (pinfunction "2_2") (pintype "passive"))
      (node (ref "C6") (pin "2") (pinfunction "2_2") (pintype "passive"))
      (node (ref "C7") (pin "2") (pinfunction "2_2") (pintype "passive"))
      (node (ref "C8") (pin "2") (pinfunction "2_2") (pintype "passive"))
      (node (ref "C9") (pin "2") (pinfunction "2_2") (pintype "passive"))
      (node (ref "D2") (pin "A") (pinfunction "A_A") (pintype "passive"))
      (node (ref "E1") (pin "12") (pinfunction "GND_12") (pintype "power_in"))
      (node (ref "E10") (pin "7") (pinfunction "GND_7") (pintype "power_in"))
      (node (ref "E11") (pin "7") (pinfunction "GND_7") (pintype "power_in"))
      (node (ref "E12") (pin "7") (pinfunction "GND_7") (pintype "power_in"))
      (node (ref "E13") (pin "7") (pinfunction "GND_7") (pintype "power_in"))
      (node (ref "E14") (pin "7") (pinfunction "GND_7") (pintype "power_in"))
      (node (ref "E15") (pin "2") (pinfunction "D_2") (pintype "input"))
      (node (ref "E15") (pin "7") (pinfunction "GND_7") (pintype "power_in"))
      (node (ref "E16") (pin "7") (pinfunction "GND_7") (pintype "power_in"))
      (node (ref "E17") (pin "7") (pinfunction "GND_7") (pintype "power_in"))
      (node (ref "E18") (pin "7") (pinfunction "GND_7") (pintype "power_in"))
      (node (ref "E19") (pin "7") (pinfunction "GND_7") (pintype "power_in"))
      (node (ref "E2") (pin "7") (pinfunction "GND_7") (pintype "power_in"))
      (node (ref "E3") (pin "7") (pinfunction "GND_7") (pintype "power_in"))
      (node (ref "E4") (pin "12") (pinfunction "GND_12") (pintype "power_in"))
      (node (ref "E5") (pin "2") (pinfunction "D_2") (pintype "input"))
      (node (ref "E5") (pin "7") (pinfunction "GND_7") (pintype "power_in"))
      (node (ref "E6") (pin "7") (pinfunction "GND_7") (pintype "power_in"))
      (node (ref "E7") (pin "7") (pinfunction "GND_7") (pintype "power_in"))
      (node (ref "E8") (pin "7") (pinfunction "GND_7") (pintype "power_in"))
      (node (ref "E8") (pin "9") (pinfunction "I_9") (pintype "input"))
      (node (ref "E9") (pin "7") (pinfunction "GND_7") (pintype "power_in"))
      (node (ref "R10") (pin "1") (pinfunction "1_1") (pintype "passive"))
      (node (ref "R4") (pin "1") (pinfunction "1_1") (pintype "passive"))
      (node (ref "R5") (pin "1") (pinfunction "1_1") (pintype "passive"))
      (node (ref "U$5") (pin "AC2") (pinfunction "1_AC2") (pintype "bidirectional"))
      (node (ref "U$5") (pin "BC2") (pinfunction "1_BC2") (pintype "bidirectional"))
      (node (ref "U$5") (pin "BT1") (pinfunction "1_BT1") (pintype "bidirectional"))
    )
    (net (code "70") (name "Net-(C16-Pad+)") (class "Default")
      (node (ref "C16") (pin "+") (pinfunction "+_+") (pintype "passive"))
      (node (ref "R11") (pin "2") (pinfunction "2_2") (pintype "passive"))
      (node (ref "R9") (pin "1") (pinfunction "1_1") (pintype "passive"))
    )
    (net (code "71") (name "Net-(C22-Pad+)") (class "Default")
      (node (ref "C22") (pin "+") (pinfunction "+_+") (pintype "passive"))
      (node (ref "D1") (pin "A") (pinfunction "A_A") (pintype "passive"))
      (node (ref "R1") (pin "1") (pinfunction "1_1") (pintype "passive"))
    )
    (net (code "72") (name "Net-(E1A-Q1)") (class "Default")
      (node (ref "E1") (pin "16") (pinfunction "Q1_16") (pintype "output"))
      (node (ref "E7") (pin "12") (pinfunction "I1_12") (pintype "input"))
    )
    (net (code "73") (name "Net-(E1A-Q3)") (class "Default")
      (node (ref "E1") (pin "10") (pinfunction "Q3_10") (pintype "output"))
      (node (ref "E7") (pin "5") (pinfunction "I0_5") (pintype "input"))
    )
    (net (code "74") (name "Net-(E2A-I1)") (class "Default")
      (node (ref "C19") (pin "1") (pinfunction "1_1") (pintype "passive"))
      (node (ref "D2") (pin "C") (pinfunction "C_C") (pintype "passive"))
      (node (ref "E2") (pin "2") (pinfunction "I1_2") (pintype "input"))
      (node (ref "R5") (pin "2") (pinfunction "2_2") (pintype "passive"))
    )
    (net (code "75") (name "Net-(E2B-I0)") (class "Default")
      (node (ref "E2") (pin "4") (pinfunction "I0_4") (pintype "input"))
      (node (ref "E3") (pin "8") (pinfunction "Q_8") (pintype "output"))
      (node (ref "E6") (pin "11") (pinfunction "I0_11") (pintype "input"))
    )
    (net (code "76") (name "Net-(E2B-O)") (class "Default")
      (node (ref "E2") (pin "6") (pinfunction "O_6") (pintype "output"))
      (node (ref "E2") (pin "9") (pinfunction "I0_9") (pintype "input"))
      (node (ref "E8") (pin "11") (pinfunction "I_11") (pintype "input"))
    )
    (net (code "77") (name "Net-(E2C-O)") (class "Default")
      (node (ref "E2") (pin "12") (pinfunction "I0_12") (pintype "input"))
      (node (ref "E2") (pin "8") (pinfunction "O_8") (pintype "output"))
    )
    (net (code "78") (name "Net-(E2D-O)") (class "Default")
      (node (ref "E2") (pin "11") (pinfunction "O_11") (pintype "output"))
      (node (ref "E8") (pin "1") (pinfunction "I_1") (pintype "input"))
    )
    (net (code "79") (name "Net-(E3A-P$5)") (class "Default")
      (node (ref "C22") (pin "-") (pinfunction "-_-") (pintype "passive"))
      (node (ref "E3") (pin "11") (pinfunction "P$5_11") (pintype "bidirectional"))
      (node (ref "E6") (pin "13") (pinfunction "O_13") (pintype "open_collector"))
    )
    (net (code "80") (name "Net-(E3A-P$6)") (class "Default")
      (node (ref "D1") (pin "C") (pinfunction "C_C") (pintype "passive"))
      (node (ref "E3") (pin "13") (pinfunction "P$6_13") (pintype "bidirectional"))
    )
    (net (code "81") (name "Net-(E4A-Q2)") (class "Default")
      (node (ref "E4") (pin "15") (pinfunction "Q2_15") (pintype "output"))
      (node (ref "E7") (pin "2") (pinfunction "I0_2") (pintype "input"))
    )
    (net (code "82") (name "Net-(E4A-Q3)") (class "Default")
      (node (ref "E4") (pin "10") (pinfunction "Q3_10") (pintype "output"))
      (node (ref "E7") (pin "9") (pinfunction "I1_9") (pintype "input"))
    )
    (net (code "83") (name "Net-(E6D-I1)") (class "Default")
      (node (ref "E6") (pin "12") (pinfunction "I1_12") (pintype "input"))
      (node (ref "E8") (pin "12") (pinfunction "O_12") (pintype "output"))
    )
    (net (code "84") (name "Net-(E9C-O)") (class "Default")
      (node (ref "C19") (pin "2") (pinfunction "2_2") (pintype "passive"))
      (node (ref "C24") (pin "1") (pinfunction "1_1") (pintype "passive"))
      (node (ref "E9") (pin "8") (pinfunction "O_8") (pintype "output"))
      (node (ref "R6") (pin "1") (pinfunction "1_1") (pintype "passive"))
    )
    (net (code "85") (name "Net-(E10A-O)") (class "Default")
      (node (ref "E10") (pin "12") (pinfunction "O_12") (pintype "output"))
      (node (ref "E15") (pin "10") (pinfunction "PRE_10") (pintype "input"))
    )
    (net (code "86") (name "Net-(E10C-O)") (class "Default")
      (node (ref "E10") (pin "8") (pinfunction "O_8") (pintype "output"))
      (node (ref "E8") (pin "5") (pinfunction "I_5") (pintype "input"))
    )
    (net (code "87") (name "Net-(E11A-I0)") (class "Default")
      (node (ref "E11") (pin "2") (pinfunction "I0_2") (pintype "input"))
      (node (ref "E4") (pin "16") (pinfunction "Q1_16") (pintype "output"))
    )
    (net (code "88") (name "Net-(E11B-I0)") (class "Default")
      (node (ref "E1") (pin "9") (pinfunction "Q4_9") (pintype "output"))
      (node (ref "E11") (pin "5") (pinfunction "I0_5") (pintype "input"))
    )
    (net (code "89") (name "Net-(E11C-I0)") (class "Default")
      (node (ref "E11") (pin "8") (pinfunction "I0_8") (pintype "input"))
      (node (ref "E4") (pin "9") (pinfunction "Q4_9") (pintype "output"))
    )
    (net (code "90") (name "Net-(E11D-I1)") (class "Default")
      (node (ref "E1") (pin "15") (pinfunction "Q2_15") (pintype "output"))
      (node (ref "E11") (pin "12") (pinfunction "I1_12") (pintype "input"))
    )
    (net (code "91") (name "Net-(E12A-I0)") (class "Default")
      (node (ref "E12") (pin "1") (pinfunction "I0_1") (pintype "input"))
      (node (ref "E12") (pin "2") (pinfunction "I1_2") (pintype "input"))
      (node (ref "E12") (pin "4") (pinfunction "I2_4") (pintype "input"))
      (node (ref "E12") (pin "5") (pinfunction "I3_5") (pintype "input"))
      (node (ref "R3") (pin "2") (pinfunction "2_2") (pintype "passive"))
    )
    (net (code "92") (name "Net-(E12B-I0)") (class "Default")
      (node (ref "E12") (pin "10") (pinfunction "I1_10") (pintype "input"))
      (node (ref "E12") (pin "12") (pinfunction "I2_12") (pintype "input"))
      (node (ref "E12") (pin "13") (pinfunction "I3_13") (pintype "input"))
      (node (ref "E12") (pin "9") (pinfunction "I0_9") (pintype "input"))
      (node (ref "E8") (pin "4") (pinfunction "O_4") (pintype "output"))
    )
    (net (code "93") (name "Net-(E13A-O)") (class "Default")
      (node (ref "E13") (pin "2") (pinfunction "O_2") (pintype "output"))
      (node (ref "E13") (pin "3") (pinfunction "I_3") (pintype "input"))
    )
    (net (code "94") (name "Net-(E13D-I)") (class "Default")
      (node (ref "E13") (pin "9") (pinfunction "I_9") (pintype "input"))
      (node (ref "E14") (pin "8") (pinfunction "O_8") (pintype "output"))
    )
    (net (code "95") (name "Net-(E13D-O)") (class "Default")
      (node (ref "E13") (pin "8") (pinfunction "O_8") (pintype "output"))
      (node (ref "E9") (pin "13") (pinfunction "I1_13") (pintype "input"))
      (node (ref "E9") (pin "2") (pinfunction "I1_2") (pintype "input"))
      (node (ref "E9") (pin "4") (pinfunction "I0_4") (pintype "input"))
    )
    (net (code "96") (name "Net-(E13F-I)") (class "Default")
      (node (ref "E13") (pin "13") (pinfunction "I_13") (pintype "input"))
      (node (ref "E9") (pin "3") (pinfunction "O_3") (pintype "output"))
    )
    (net (code "97") (name "Net-(E15A-~{Q})") (class "Default")
      (node (ref "E15") (pin "6") (pinfunction "~{Q}_6") (pintype "output"))
      (node (ref "E17") (pin "9") (pinfunction "I_9") (pintype "input"))
    )
    (net (code "98") (name "Net-(E16A-I1)") (class "Default")
      (node (ref "E16") (pin "2") (pinfunction "I1_2") (pintype "input"))
      (node (ref "E17") (pin "11") (pinfunction "I_11") (pintype "input"))
      (node (ref "E18") (pin "8") (pinfunction "~{Q}_8") (pintype "output"))
    )
    (net (code "99") (name "Net-(E16A-O)") (class "Default")
      (node (ref "E16") (pin "3") (pinfunction "O_3") (pintype "output"))
      (node (ref "E16") (pin "4") (pinfunction "I0_4") (pintype "input"))
    )
    (net (code "100") (name "Net-(E16B-I1)") (class "Default")
      (node (ref "E16") (pin "5") (pinfunction "I1_5") (pintype "input"))
      (node (ref "E19") (pin "6") (pinfunction "O_6") (pintype "output"))
    )
    (net (code "101") (name "Net-(E16D-O)") (class "Default")
      (node (ref "E16") (pin "11") (pinfunction "O_11") (pintype "output"))
      (node (ref "R3") (pin "1") (pinfunction "1_1") (pintype "passive"))
    )
    (net (code "102") (name "Net-(E17A-I)") (class "Default")
      (node (ref "E17") (pin "1") (pinfunction "I_1") (pintype "input"))
      (node (ref "E18") (pin "2") (pinfunction "D_2") (pintype "input"))
      (node (ref "E18") (pin "9") (pinfunction "Q_9") (pintype "output"))
      (node (ref "E19") (pin "4") (pinfunction "I0_4") (pintype "input"))
    )
    (net (code "103") (name "Net-(E17B-I)") (class "Default")
      (node (ref "E17") (pin "3") (pinfunction "I_3") (pintype "input"))
      (node (ref "E18") (pin "5") (pinfunction "Q_5") (pintype "output"))
      (node (ref "E19") (pin "5") (pinfunction "I1_5") (pintype "input"))
    )
    (net (code "104") (name "Net-(E17F-I)") (class "Default")
      (node (ref "E17") (pin "13") (pinfunction "I_13") (pintype "input"))
      (node (ref "Q1") (pin "2") (pinfunction "B_2") (pintype "passive"))
      (node (ref "Q2") (pin "3") (pinfunction "C_3") (pintype "passive"))
      (node (ref "R12") (pin "1") (pinfunction "1_1") (pintype "passive"))
    )
    (net (code "105") (name "Net-(E17F-O)") (class "Default")
      (node (ref "E17") (pin "12") (pinfunction "O_12") (pintype "output"))
      (node (ref "E19") (pin "10") (pinfunction "I1_10") (pintype "input"))
      (node (ref "E3") (pin "1") (pinfunction "P$1_1") (pintype "input"))
      (node (ref "E3") (pin "2") (pinfunction "P$2_2") (pintype "input"))
      (node (ref "R15") (pin "1") (pinfunction "1_1") (pintype "passive"))
      (node (ref "R16") (pin "1") (pinfunction "1_1") (pintype "passive"))
    )
    (net (code "106") (name "Net-(E19C-I0)") (class "Default")
      (node (ref "E19") (pin "11") (pinfunction "O_11") (pintype "output"))
      (node (ref "E19") (pin "9") (pinfunction "I0_9") (pintype "input"))
      (node (ref "E8") (pin "13") (pinfunction "I_13") (pintype "input"))
    )
    (net (code "107") (name "Net-(E19C-O)") (class "Default")
      (node (ref "E19") (pin "12") (pinfunction "I0_12") (pintype "input"))
      (node (ref "E19") (pin "8") (pinfunction "O_8") (pintype "output"))
    )
    (net (code "108") (name "Net-(Q1-C)") (class "Default")
      (node (ref "Q1") (pin "3") (pinfunction "C_3") (pintype "passive"))
      (node (ref "R13") (pin "1") (pinfunction "1_1") (pintype "passive"))
    )
    (net (code "109") (name "Net-(Q1-E)") (class "Default")
      (node (ref "Q1") (pin "1") (pinfunction "E_1") (pintype "passive"))
      (node (ref "Q2") (pin "1") (pinfunction "E_1") (pintype "passive"))
      (node (ref "R10") (pin "2") (pinfunction "2_2") (pintype "passive"))
    )
    (net (code "110") (name "Net-(Q2-B)") (class "Default")
      (node (ref "Q2") (pin "2") (pinfunction "B_2") (pintype "passive"))
      (node (ref "R9") (pin "2") (pinfunction "2_2") (pintype "passive"))
    )
    (net (code "111") (name "unconnected-(E1A-~{Q1}-Pad1)") (class "Default")
      (node (ref "E1") (pin "1") (pinfunction "~{Q1}_1") (pintype "output"))
    )
    (net (code "112") (name "unconnected-(E1A-~{Q2}-Pad14)") (class "Default")
      (node (ref "E1") (pin "14") (pinfunction "~{Q2}_14") (pintype "output"))
    )
    (net (code "113") (name "unconnected-(E1A-~{Q3}-Pad11)") (class "Default")
      (node (ref "E1") (pin "11") (pinfunction "~{Q3}_11") (pintype "output"))
    )
    (net (code "114") (name "unconnected-(E1A-~{Q4}-Pad8)") (class "Default")
      (node (ref "E1") (pin "8") (pinfunction "~{Q4}_8") (pintype "output"))
    )
    (net (code "115") (name "unconnected-(E3A-~{Q}-Pad6)") (class "Default")
      (node (ref "E3") (pin "6") (pinfunction "~{Q}_6") (pintype "output"))
    )
    (net (code "116") (name "unconnected-(E4A-~{Q1}-Pad1)") (class "Default")
      (node (ref "E4") (pin "1") (pinfunction "~{Q1}_1") (pintype "output"))
    )
    (net (code "117") (name "unconnected-(E4A-~{Q2}-Pad14)") (class "Default")
      (node (ref "E4") (pin "14") (pinfunction "~{Q2}_14") (pintype "output"))
    )
    (net (code "118") (name "unconnected-(E4A-~{Q3}-Pad11)") (class "Default")
      (node (ref "E4") (pin "11") (pinfunction "~{Q3}_11") (pintype "output"))
    )
    (net (code "119") (name "unconnected-(E4A-~{Q4}-Pad8)") (class "Default")
      (node (ref "E4") (pin "8") (pinfunction "~{Q4}_8") (pintype "output"))
    )
    (net (code "120") (name "unconnected-(E5B-~{Q}-Pad8)") (class "Default")
      (node (ref "E5") (pin "8") (pinfunction "~{Q}_8") (pintype "output"))
    )
    (net (code "121") (name "unconnected-(E8D-O-Pad8)") (class "Default")
      (node (ref "E8") (pin "8") (pinfunction "O_8") (pintype "output"))
    )
    (net (code "122") (name "unconnected-(E12B-O-Pad8)") (class "Default")
      (node (ref "E12") (pin "8") (pinfunction "O_8") (pintype "output"))
    )
    (net (code "123") (name "unconnected-(E15A-Q-Pad5)") (class "Default")
      (node (ref "E15") (pin "5") (pinfunction "Q_5") (pintype "output"))
    )
  )
)
